# large.net
KiCad netlist of a schematic drawn in EAGLE
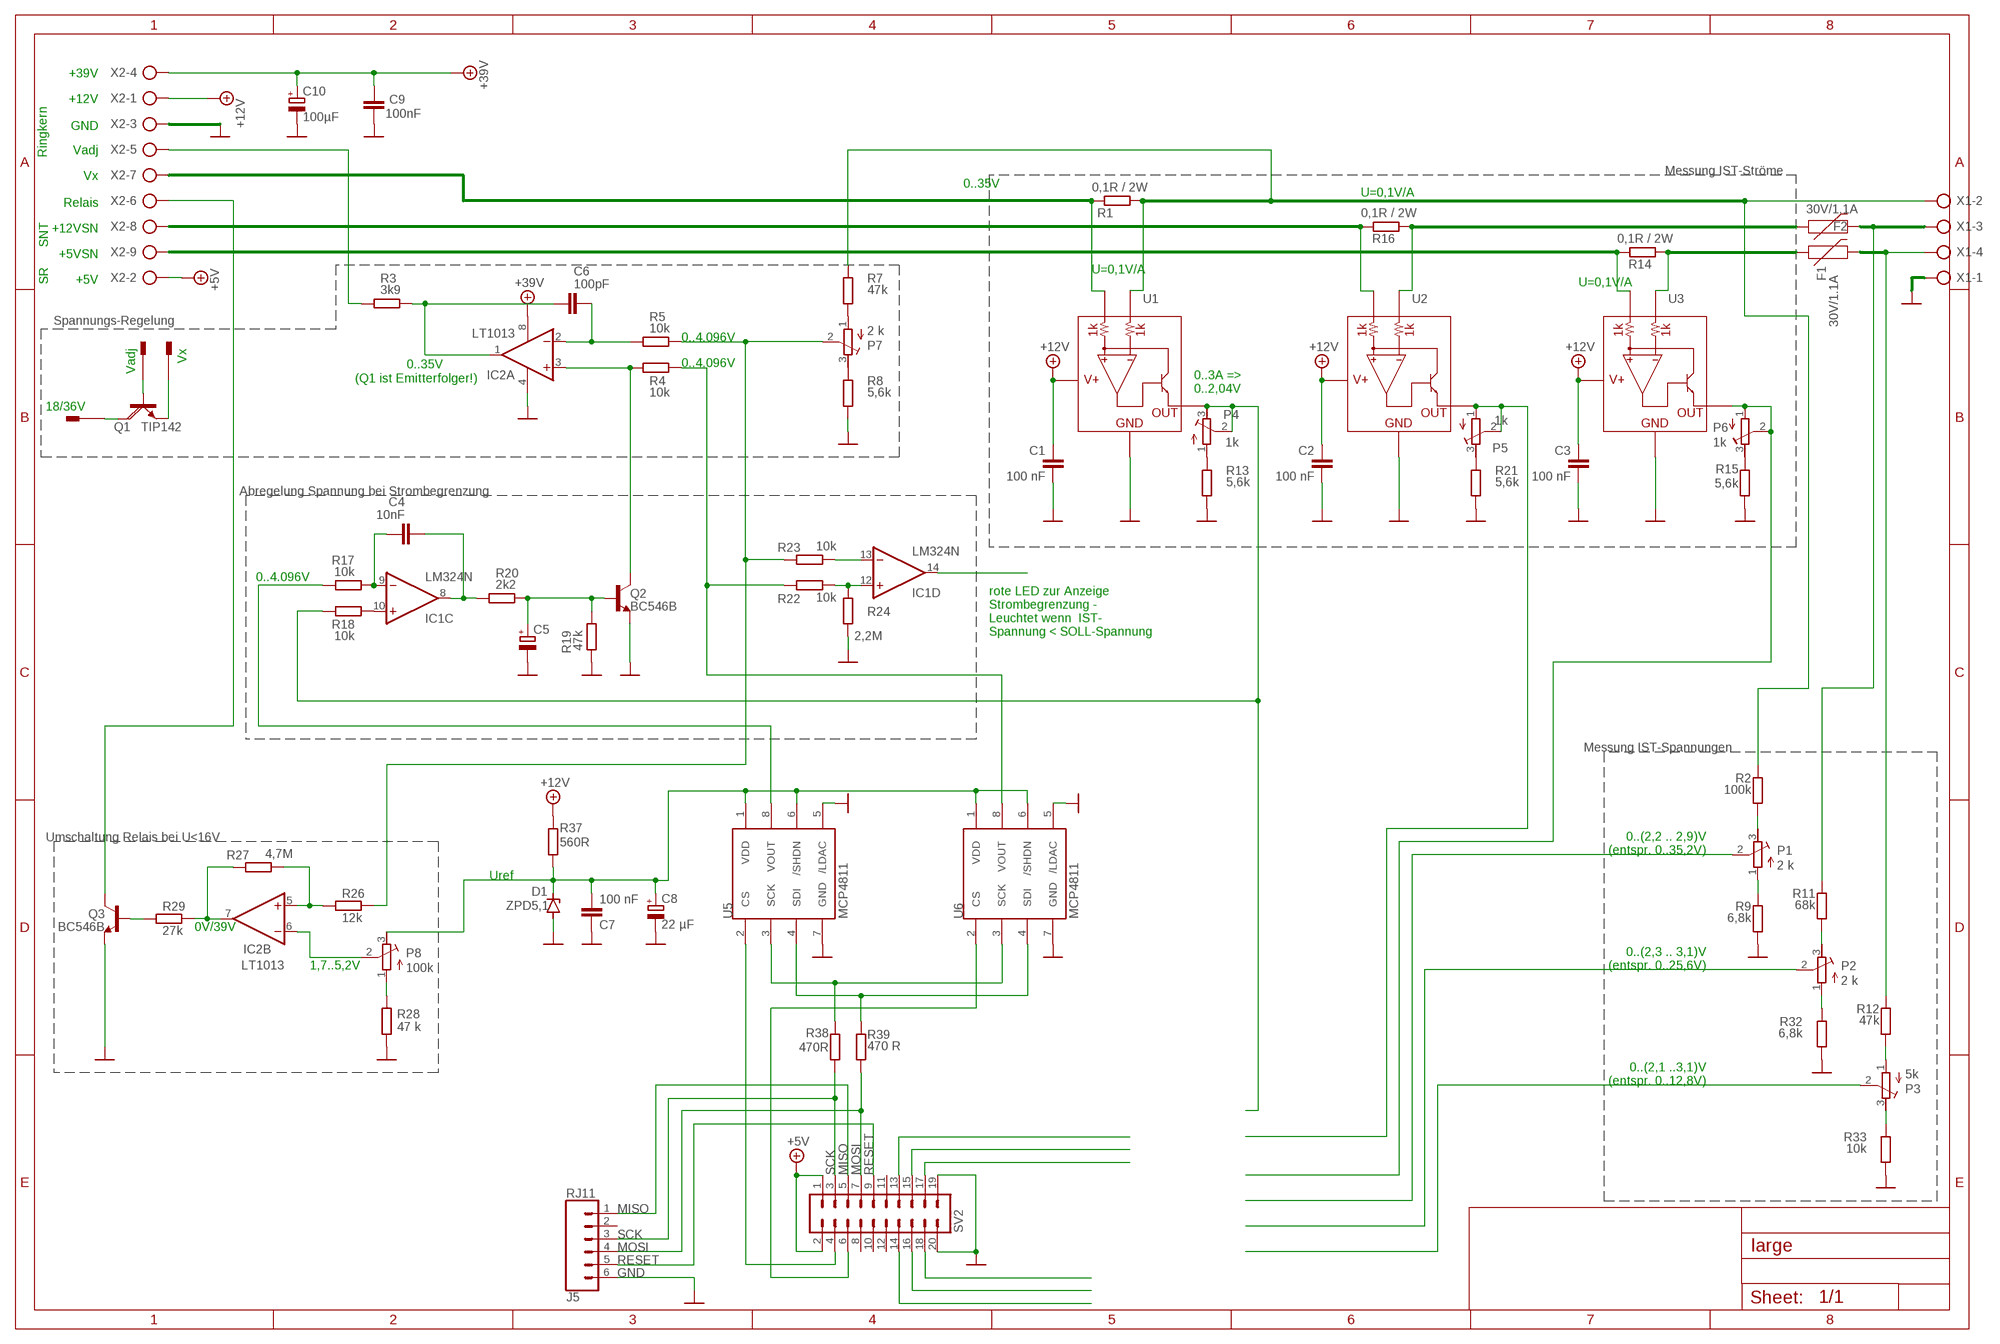
[diagram p0: schematic, sheet 1]

(export (version "E")
  (design (tool "Eeschema 10.0.6"))
  (components
    (comp (ref "C1")
      (value "100 nF")
      (footprint "eagle-import:C025-025X050")
      (libsource (lib "eagle-import") (part "C-EU025-025X050"))
    )
    (comp (ref "C2")
      (value "100 nF")
      (footprint "eagle-import:C025-025X050")
      (libsource (lib "eagle-import") (part "C-EU025-025X050"))
    )
    (comp (ref "C3")
      (value "100 nF")
      (footprint "eagle-import:C025-025X050")
      (libsource (lib "eagle-import") (part "C-EU025-025X050"))
    )
    (comp (ref "C4")
      (value "10nF")
      (footprint "eagle-import:C025-025X050")
      (libsource (lib "eagle-import") (part "C-EU025-025X050"))
    )
    (comp (ref "C5")
      (value "CPOL-EUE2-4")
      (footprint "eagle-import:E2-4")
      (libsource (lib "eagle-import") (part "CPOL-EUE2-4"))
    )
    (comp (ref "C6")
      (value "100pF")
      (footprint "eagle-import:C025-025X050")
      (libsource (lib "eagle-import") (part "C-EU025-025X050"))
    )
    (comp (ref "C7")
      (value "100 nF")
      (footprint "eagle-import:C025-025X050")
      (libsource (lib "eagle-import") (part "C-EU025-025X050"))
    )
    (comp (ref "C8")
      (value "22 µF")
      (footprint "eagle-import:E2-5")
      (libsource (lib "eagle-import") (part "CPOL-EUE2-5"))
    )
    (comp (ref "C9")
      (value "100nF")
      (footprint "eagle-import:C025-025X050")
      (libsource (lib "eagle-import") (part "C-EU025-025X050"))
    )
    (comp (ref "C10")
      (value "100µF")
      (footprint "eagle-import:E2-5")
      (libsource (lib "eagle-import") (part "CPOL-EUE2-5"))
    )
    (comp (ref "D1")
      (value "ZPD5,1")
      (footprint "eagle-import:ZDIO-5")
      (libsource (lib "eagle-import") (part "ZENER-DIODEZD-5"))
    )
    (comp (ref "F1")
      (value "30V/1.1A")
      (footprint "eagle-import:PTH")
      (libsource (lib "eagle-import") (part "PPTC_PTH"))
    )
    (comp (ref "F2")
      (value "30V/1.1A")
      (footprint "eagle-import:PTH")
      (libsource (lib "eagle-import") (part "PPTC_PTH"))
    )
    (comp (ref "IC1")
      (value "LM324N")
      (footprint "eagle-import:DIL14")
      (libsource (lib "eagle-import") (part "LM324N"))
    )
    (comp (ref "IC2")
      (value "LT1013")
      (footprint "eagle-import:DIL08")
      (libsource (lib "eagle-import") (part "OPA1013P"))
    )
    (comp (ref "J2")
      (value "PIN1-2")
      (footprint "eagle-import:62221")
      (fields (field (name "MF") "TYCO ELECTRONICS") (field (name "MPN") "62221-1"))
      (libsource (lib "eagle-import") (part "PIN1-2"))
    )
    (comp (ref "J3")
      (value "PIN1-2")
      (footprint "eagle-import:62221")
      (fields (field (name "MF") "TYCO ELECTRONICS") (field (name "MPN") "62221-1"))
      (libsource (lib "eagle-import") (part "PIN1-2"))
    )
    (comp (ref "J4")
      (value "PIN1-2")
      (footprint "eagle-import:62221")
      (fields (field (name "MF") "TYCO ELECTRONICS") (field (name "MPN") "62221-1"))
      (libsource (lib "eagle-import") (part "PIN1-2"))
    )
    (comp (ref "J5")
      (value "RJ11")
      (footprint "eagle-import:RJ11-6")
      (libsource (lib "eagle-import") (part "RJ11-6"))
    )
    (comp (ref "P1")
      (value "2 k")
      (footprint "eagle-import:RTRIM64Y")
      (libsource (lib "eagle-import") (part "R-TRIMM64Y"))
    )
    (comp (ref "P2")
      (value "2 k")
      (footprint "eagle-import:RTRIM64Y")
      (libsource (lib "eagle-import") (part "R-TRIMM64Y"))
    )
    (comp (ref "P3")
      (value "5k")
      (footprint "eagle-import:RTRIM64Y")
      (libsource (lib "eagle-import") (part "R-TRIMM64Y"))
    )
    (comp (ref "P4")
      (value "1k")
      (footprint "eagle-import:RTRIM64Z")
      (libsource (lib "eagle-import") (part "R-TRIMM64Z"))
    )
    (comp (ref "P5")
      (value "1k")
      (footprint "eagle-import:RTRIM64Y")
      (libsource (lib "eagle-import") (part "R-TRIMM64Y"))
    )
    (comp (ref "P6")
      (value "1k")
      (footprint "eagle-import:RTRIM64Y")
      (libsource (lib "eagle-import") (part "R-TRIMM64Y"))
    )
    (comp (ref "P7")
      (value "2 k")
      (footprint "eagle-import:RTRIM64Y")
      (libsource (lib "eagle-import") (part "R-TRIMM64Y"))
    )
    (comp (ref "P8")
      (value "100k")
      (footprint "eagle-import:RTRIM64Z")
      (libsource (lib "eagle-import") (part "R-TRIMM64Z"))
    )
    (comp (ref "Q1")
      (value "TIP142")
      (footprint "eagle-import:SOT93")
      (libsource (lib "eagle-import") (part "TIP142"))
    )
    (comp (ref "Q2")
      (value "BC546B")
      (footprint "eagle-import:TO92-EBC")
      (libsource (lib "eagle-import") (part "BC546A"))
    )
    (comp (ref "Q3")
      (value "BC546B")
      (footprint "eagle-import:TO92-EBC")
      (libsource (lib "eagle-import") (part "BC546A"))
    )
    (comp (ref "R1")
      (value "0,1R / 2W")
      (footprint "eagle-import:0617_17")
      (libsource (lib "eagle-import") (part "R-EU_0617/17"))
    )
    (comp (ref "R2")
      (value "100k")
      (footprint "eagle-import:0204_7")
      (libsource (lib "eagle-import") (part "R-EU_0204/7"))
    )
    (comp (ref "R3")
      (value "3k9")
      (footprint "eagle-import:0204_7")
      (libsource (lib "eagle-import") (part "R-EU_0204/7"))
    )
    (comp (ref "R4")
      (value "10k")
      (footprint "eagle-import:0204_7")
      (libsource (lib "eagle-import") (part "R-EU_0204/7"))
    )
    (comp (ref "R5")
      (value "10k")
      (footprint "eagle-import:0204_7")
      (libsource (lib "eagle-import") (part "R-EU_0204/7"))
    )
    (comp (ref "R7")
      (value "47k")
      (footprint "eagle-import:0204_7")
      (libsource (lib "eagle-import") (part "R-EU_0204/7"))
    )
    (comp (ref "R8")
      (value "5,6k")
      (footprint "eagle-import:0204_7")
      (libsource (lib "eagle-import") (part "R-EU_0204/7"))
    )
    (comp (ref "R9")
      (value "6,8k")
      (footprint "eagle-import:0204_7")
      (libsource (lib "eagle-import") (part "R-EU_0204/7"))
    )
    (comp (ref "R11")
      (value "68k")
      (footprint "eagle-import:0204_7")
      (libsource (lib "eagle-import") (part "R-EU_0204/7"))
    )
    (comp (ref "R12")
      (value "47k")
      (footprint "eagle-import:0204_7")
      (libsource (lib "eagle-import") (part "R-EU_0204/7"))
    )
    (comp (ref "R13")
      (value "5,6k")
      (footprint "eagle-import:0204_7")
      (libsource (lib "eagle-import") (part "R-EU_0204/7"))
    )
    (comp (ref "R14")
      (value "0,1R / 2W")
      (footprint "eagle-import:0617_17")
      (libsource (lib "eagle-import") (part "R-EU_0617/17"))
    )
    (comp (ref "R15")
      (value "5,6k")
      (footprint "eagle-import:0204_5")
      (libsource (lib "eagle-import") (part "R-EU_0204/5"))
    )
    (comp (ref "R16")
      (value "0,1R / 2W")
      (footprint "eagle-import:0617_17")
      (libsource (lib "eagle-import") (part "R-EU_0617/17"))
    )
    (comp (ref "R17")
      (value "10k")
      (footprint "eagle-import:0204_5")
      (libsource (lib "eagle-import") (part "R-EU_0204/5"))
    )
    (comp (ref "R18")
      (value "10k")
      (footprint "eagle-import:0204_5")
      (libsource (lib "eagle-import") (part "R-EU_0204/5"))
    )
    (comp (ref "R19")
      (value "47k")
      (footprint "eagle-import:0204_5")
      (libsource (lib "eagle-import") (part "R-EU_0204/5"))
    )
    (comp (ref "R20")
      (value "2k2")
      (footprint "eagle-import:0204_5")
      (libsource (lib "eagle-import") (part "R-EU_0204/5"))
    )
    (comp (ref "R21")
      (value "5,6k")
      (footprint "eagle-import:0204_7")
      (libsource (lib "eagle-import") (part "R-EU_0204/7"))
    )
    (comp (ref "R22")
      (value "10k")
      (footprint "eagle-import:0204_5")
      (libsource (lib "eagle-import") (part "R-EU_0204/5"))
    )
    (comp (ref "R23")
      (value "10k")
      (footprint "eagle-import:0204_5")
      (libsource (lib "eagle-import") (part "R-EU_0204/5"))
    )
    (comp (ref "R24")
      (value "2,2M")
      (footprint "eagle-import:0204_5")
      (libsource (lib "eagle-import") (part "R-EU_0204/5"))
    )
    (comp (ref "R26")
      (value "12k")
      (footprint "eagle-import:0204_5")
      (libsource (lib "eagle-import") (part "R-EU_0204/5"))
    )
    (comp (ref "R27")
      (value "4,7M")
      (footprint "eagle-import:0204_5")
      (libsource (lib "eagle-import") (part "R-EU_0204/5"))
    )
    (comp (ref "R28")
      (value "47 k")
      (footprint "eagle-import:0204_5")
      (libsource (lib "eagle-import") (part "R-EU_0204/5"))
    )
    (comp (ref "R29")
      (value "27k")
      (footprint "eagle-import:0204_7")
      (libsource (lib "eagle-import") (part "R-EU_0204/7"))
    )
    (comp (ref "R32")
      (value "6,8k")
      (footprint "eagle-import:0204_7")
      (libsource (lib "eagle-import") (part "R-EU_0204/7"))
    )
    (comp (ref "R33")
      (value "10k")
      (footprint "eagle-import:0204_7")
      (libsource (lib "eagle-import") (part "R-EU_0204/7"))
    )
    (comp (ref "R37")
      (value "560R")
      (footprint "eagle-import:0204_7")
      (libsource (lib "eagle-import") (part "R-EU_0204/7"))
    )
    (comp (ref "R38")
      (value "470R")
      (footprint "eagle-import:0204_7")
      (libsource (lib "eagle-import") (part "R-EU_0204/7"))
    )
    (comp (ref "R39")
      (value "470 R")
      (footprint "eagle-import:0204_7")
      (libsource (lib "eagle-import") (part "R-EU_0204/7"))
    )
    (comp (ref "SV2")
      (value "MA10-2")
      (footprint "eagle-import:MA10-2")
      (libsource (lib "eagle-import") (part "MA10-2"))
    )
    (comp (ref "U1")
      (value "INA139DIL06")
      (footprint "eagle-import:DIL06")
      (libsource (lib "eagle-import") (part "INA139DIL06"))
    )
    (comp (ref "U2")
      (value "INA139DIL06")
      (footprint "eagle-import:DIL06")
      (libsource (lib "eagle-import") (part "INA139DIL06"))
    )
    (comp (ref "U3")
      (value "INA139DIL06")
      (footprint "eagle-import:DIL06")
      (libsource (lib "eagle-import") (part "INA139DIL06"))
    )
    (comp (ref "U5")
      (value "MCP4811")
      (footprint "eagle-import:PDIP8")
      (libsource (lib "eagle-import") (part "MCP4811"))
    )
    (comp (ref "U6")
      (value "MCP4811")
      (footprint "eagle-import:PDIP8")
      (libsource (lib "eagle-import") (part "MCP4811"))
    )
    (comp (ref "X1")
      (value "AK500/4")
      (footprint "eagle-import:AK500_4")
      (libsource (lib "eagle-import") (part "AK500/4"))
    )
    (comp (ref "X2")
      (value "AK500/9")
      (footprint "eagle-import:AK500_9")
      (libsource (lib "eagle-import") (part "AK500/9"))
    )
  )
  (nets
    (net (code "1") (name "+5V") (class "Default")
      (node (ref "SV2") (pin "1") (pinfunction "1_1") (pintype "passive"))
      (node (ref "SV2") (pin "2") (pinfunction "2_2") (pintype "passive"))
      (node (ref "X2") (pin "2") (pinfunction "KL_2") (pintype "passive"))
    )
    (net (code "2") (name "+12V") (class "Default")
      (node (ref "C1") (pin "2") (pinfunction "2_2") (pintype "passive"))
      (node (ref "C2") (pin "2") (pinfunction "2_2") (pintype "passive"))
      (node (ref "C3") (pin "2") (pinfunction "2_2") (pintype "passive"))
      (node (ref "R37") (pin "1") (pinfunction "1_1") (pintype "passive"))
      (node (ref "U1") (pin "6") (pinfunction "V+_6") (pintype "bidirectional"))
      (node (ref "U2") (pin "6") (pinfunction "V+_6") (pintype "bidirectional"))
      (node (ref "U3") (pin "6") (pinfunction "V+_6") (pintype "bidirectional"))
      (node (ref "X2") (pin "1") (pinfunction "KL_1") (pintype "passive"))
    )
    (net (code "3") (name "+39V") (class "Default")
      (node (ref "C10") (pin "+") (pinfunction "+_+") (pintype "passive"))
      (node (ref "C9") (pin "2") (pinfunction "2_2") (pintype "passive"))
      (node (ref "IC2") (pin "8") (pinfunction "V+_8") (pintype "power_in"))
      (node (ref "X2") (pin "4") (pinfunction "KL_4") (pintype "passive"))
    )
    (net (code "4") (name "/MISO") (class "Default")
      (node (ref "J5") (pin "1") (pinfunction "1_1") (pintype "passive"))
      (node (ref "SV2") (pin "5") (pinfunction "5_5") (pintype "passive"))
    )
    (net (code "5") (name "/MOSI") (class "Default")
      (node (ref "J5") (pin "4") (pinfunction "4_4") (pintype "passive"))
      (node (ref "R39") (pin "1") (pinfunction "1_1") (pintype "passive"))
      (node (ref "SV2") (pin "7") (pinfunction "7_7") (pintype "passive"))
    )
    (net (code "6") (name "/RESET") (class "Default")
      (node (ref "J5") (pin "5") (pinfunction "5_5") (pintype "passive"))
      (node (ref "SV2") (pin "9") (pinfunction "9_9") (pintype "passive"))
    )
    (net (code "7") (name "/SCK") (class "Default")
      (node (ref "J5") (pin "3") (pinfunction "3_3") (pintype "passive"))
      (node (ref "R38") (pin "1") (pinfunction "1_1") (pintype "passive"))
      (node (ref "SV2") (pin "3") (pinfunction "3_3") (pintype "passive"))
    )
    (net (code "8") (name "GND") (class "Default")
      (node (ref "C1") (pin "1") (pinfunction "1_1") (pintype "passive"))
      (node (ref "C10") (pin "-") (pinfunction "-_-") (pintype "passive"))
      (node (ref "C2") (pin "1") (pinfunction "1_1") (pintype "passive"))
      (node (ref "C3") (pin "1") (pinfunction "1_1") (pintype "passive"))
      (node (ref "C5") (pin "-") (pinfunction "-_-") (pintype "passive"))
      (node (ref "C7") (pin "2") (pinfunction "2_2") (pintype "passive"))
      (node (ref "C8") (pin "-") (pinfunction "-_-") (pintype "passive"))
      (node (ref "C9") (pin "1") (pinfunction "1_1") (pintype "passive"))
      (node (ref "D1") (pin "A") (pinfunction "A_A") (pintype "passive"))
      (node (ref "IC2") (pin "4") (pinfunction "V-_4") (pintype "power_in"))
      (node (ref "J5") (pin "6") (pinfunction "6_6") (pintype "passive"))
      (node (ref "Q2") (pin "E") (pinfunction "E_E") (pintype "passive"))
      (node (ref "Q3") (pin "E") (pinfunction "E_E") (pintype "passive"))
      (node (ref "R13") (pin "1") (pinfunction "1_1") (pintype "passive"))
      (node (ref "R15") (pin "1") (pinfunction "1_1") (pintype "passive"))
      (node (ref "R19") (pin "2") (pinfunction "2_2") (pintype "passive"))
      (node (ref "R21") (pin "1") (pinfunction "1_1") (pintype "passive"))
      (node (ref "R24") (pin "1") (pinfunction "1_1") (pintype "passive"))
      (node (ref "R28") (pin "1") (pinfunction "1_1") (pintype "passive"))
      (node (ref "R32") (pin "1") (pinfunction "1_1") (pintype "passive"))
      (node (ref "R33") (pin "1") (pinfunction "1_1") (pintype "passive"))
      (node (ref "R8") (pin "1") (pinfunction "1_1") (pintype "passive"))
      (node (ref "R9") (pin "1") (pinfunction "1_1") (pintype "passive"))
      (node (ref "SV2") (pin "19") (pinfunction "19_19") (pintype "passive"))
      (node (ref "SV2") (pin "20") (pinfunction "20_20") (pintype "passive"))
      (node (ref "U1") (pin "2") (pinfunction "GND_2") (pintype "bidirectional"))
      (node (ref "U2") (pin "2") (pinfunction "GND_2") (pintype "bidirectional"))
      (node (ref "U3") (pin "2") (pinfunction "GND_2") (pintype "bidirectional"))
      (node (ref "U5") (pin "5") (pinfunction "/LDAC_5") (pintype "bidirectional"))
      (node (ref "U5") (pin "7") (pinfunction "GND_7") (pintype "bidirectional"))
      (node (ref "U6") (pin "5") (pinfunction "/LDAC_5") (pintype "bidirectional"))
      (node (ref "U6") (pin "7") (pinfunction "GND_7") (pintype "bidirectional"))
      (node (ref "X1") (pin "1") (pinfunction "KL_1") (pintype "passive"))
      (node (ref "X2") (pin "3") (pinfunction "KL_3") (pintype "passive"))
    )
    (net (code "9") (name "Net-(C5-Pad+)") (class "Default")
      (node (ref "C5") (pin "+") (pinfunction "+_+") (pintype "passive"))
      (node (ref "Q2") (pin "B") (pinfunction "B_B") (pintype "passive"))
      (node (ref "R19") (pin "1") (pinfunction "1_1") (pintype "passive"))
      (node (ref "R20") (pin "2") (pinfunction "2_2") (pintype "passive"))
    )
    (net (code "10") (name "Net-(F1-1)") (class "Default")
      (node (ref "F1") (pin "P$1") (pinfunction "1_P$1") (pintype "bidirectional"))
      (node (ref "R14") (pin "1") (pinfunction "1_1") (pintype "passive"))
      (node (ref "U3") (pin "4") (pinfunction "VIN-_4") (pintype "bidirectional"))
    )
    (net (code "11") (name "Net-(F1-2)") (class "Default")
      (node (ref "F1") (pin "P$2") (pinfunction "2_P$2") (pintype "bidirectional"))
      (node (ref "R12") (pin "2") (pinfunction "2_2") (pintype "passive"))
      (node (ref "X1") (pin "4") (pinfunction "KL_4") (pintype "passive"))
    )
    (net (code "12") (name "Net-(F2-1)") (class "Default")
      (node (ref "F2") (pin "P$1") (pinfunction "1_P$1") (pintype "bidirectional"))
      (node (ref "R16") (pin "1") (pinfunction "1_1") (pintype "passive"))
      (node (ref "U2") (pin "4") (pinfunction "VIN-_4") (pintype "bidirectional"))
    )
    (net (code "13") (name "Net-(F2-2)") (class "Default")
      (node (ref "F2") (pin "P$2") (pinfunction "2_P$2") (pintype "bidirectional"))
      (node (ref "R11") (pin "2") (pinfunction "2_2") (pintype "passive"))
      (node (ref "X1") (pin "3") (pinfunction "KL_3") (pintype "passive"))
    )
    (net (code "14") (name "Net-(IC1C-+IN)") (class "Default")
      (node (ref "IC1") (pin "10") (pinfunction "+IN_10") (pintype "input"))
      (node (ref "R18") (pin "1") (pinfunction "1_1") (pintype "passive"))
    )
    (net (code "15") (name "Net-(IC1C--IN)") (class "Default")
      (node (ref "C4") (pin "2") (pinfunction "2_2") (pintype "passive"))
      (node (ref "IC1") (pin "9") (pinfunction "-IN_9") (pintype "input"))
      (node (ref "R17") (pin "1") (pinfunction "1_1") (pintype "passive"))
    )
    (net (code "16") (name "Net-(IC1C-OUT)") (class "Default")
      (node (ref "C4") (pin "1") (pinfunction "1_1") (pintype "passive"))
      (node (ref "IC1") (pin "8") (pinfunction "OUT_8") (pintype "output"))
      (node (ref "R20") (pin "1") (pinfunction "1_1") (pintype "passive"))
    )
    (net (code "17") (name "Net-(IC1D-+IN)") (class "Default")
      (node (ref "IC1") (pin "12") (pinfunction "+IN_12") (pintype "input"))
      (node (ref "R22") (pin "2") (pinfunction "2_2") (pintype "passive"))
      (node (ref "R24") (pin "2") (pinfunction "2_2") (pintype "passive"))
    )
    (net (code "18") (name "Net-(IC1D--IN)") (class "Default")
      (node (ref "IC1") (pin "13") (pinfunction "-IN_13") (pintype "input"))
      (node (ref "R23") (pin "2") (pinfunction "2_2") (pintype "passive"))
    )
    (net (code "19") (name "Net-(IC2A-+IN)") (class "Default")
      (node (ref "IC2") (pin "3") (pinfunction "+IN_3") (pintype "input"))
      (node (ref "Q2") (pin "C") (pinfunction "C_C") (pintype "passive"))
      (node (ref "R4") (pin "1") (pinfunction "1_1") (pintype "passive"))
    )
    (net (code "20") (name "Net-(IC2A--IN)") (class "Default")
      (node (ref "C6") (pin "2") (pinfunction "2_2") (pintype "passive"))
      (node (ref "IC2") (pin "2") (pinfunction "-IN_2") (pintype "input"))
      (node (ref "R5") (pin "1") (pinfunction "1_1") (pintype "passive"))
    )
    (net (code "21") (name "Net-(IC2A-OUT)") (class "Default")
      (node (ref "C6") (pin "1") (pinfunction "1_1") (pintype "passive"))
      (node (ref "IC2") (pin "1") (pinfunction "OUT_1") (pintype "output"))
      (node (ref "R3") (pin "2") (pinfunction "2_2") (pintype "passive"))
    )
    (net (code "22") (name "Net-(IC2B-+IN)") (class "Default")
      (node (ref "IC2") (pin "5") (pinfunction "+IN_5") (pintype "input"))
      (node (ref "R26") (pin "1") (pinfunction "1_1") (pintype "passive"))
      (node (ref "R27") (pin "2") (pinfunction "2_2") (pintype "passive"))
    )
    (net (code "23") (name "Net-(IC2B--IN)") (class "Default")
      (node (ref "IC2") (pin "6") (pinfunction "-IN_6") (pintype "input"))
      (node (ref "P8") (pin "2") (pinfunction "S_2") (pintype "passive"))
    )
    (net (code "24") (name "Net-(IC2B-OUT)") (class "Default")
      (node (ref "IC2") (pin "7") (pinfunction "OUT_7") (pintype "output"))
      (node (ref "R27") (pin "1") (pinfunction "1_1") (pintype "passive"))
      (node (ref "R29") (pin "2") (pinfunction "2_2") (pintype "passive"))
    )
    (net (code "25") (name "Net-(J2-Pad1)") (class "Default")
      (node (ref "J2") (pin "1") (pinfunction "1_1") (pintype "passive"))
      (node (ref "Q1") (pin "C") (pinfunction "C_C") (pintype "passive"))
    )
    (net (code "26") (name "Net-(J3-Pad1)") (class "Default")
      (node (ref "J3") (pin "1") (pinfunction "1_1") (pintype "passive"))
      (node (ref "Q1") (pin "B") (pinfunction "B_B") (pintype "passive"))
    )
    (net (code "27") (name "Net-(J4-Pad1)") (class "Default")
      (node (ref "J4") (pin "1") (pinfunction "1_1") (pintype "passive"))
      (node (ref "Q1") (pin "E") (pinfunction "E_E") (pintype "passive"))
    )
    (net (code "28") (name "Net-(P1-A)") (class "Default")
      (node (ref "P1") (pin "1") (pinfunction "A_1") (pintype "passive"))
      (node (ref "R9") (pin "2") (pinfunction "2_2") (pintype "passive"))
    )
    (net (code "29") (name "Net-(P1-E)") (class "Default")
      (node (ref "P1") (pin "3") (pinfunction "E_3") (pintype "passive"))
      (node (ref "R2") (pin "1") (pinfunction "1_1") (pintype "passive"))
    )
    (net (code "30") (name "Net-(P2-A)") (class "Default")
      (node (ref "P2") (pin "1") (pinfunction "A_1") (pintype "passive"))
      (node (ref "R32") (pin "2") (pinfunction "2_2") (pintype "passive"))
    )
    (net (code "31") (name "Net-(P2-E)") (class "Default")
      (node (ref "P2") (pin "3") (pinfunction "E_3") (pintype "passive"))
      (node (ref "R11") (pin "1") (pinfunction "1_1") (pintype "passive"))
    )
    (net (code "32") (name "Net-(P3-A)") (class "Default")
      (node (ref "P3") (pin "1") (pinfunction "A_1") (pintype "passive"))
      (node (ref "R12") (pin "1") (pinfunction "1_1") (pintype "passive"))
    )
    (net (code "33") (name "Net-(P3-E)") (class "Default")
      (node (ref "P3") (pin "3") (pinfunction "E_3") (pintype "passive"))
      (node (ref "R33") (pin "2") (pinfunction "2_2") (pintype "passive"))
    )
    (net (code "34") (name "Net-(P4-A)") (class "Default")
      (node (ref "P4") (pin "1") (pinfunction "A_1") (pintype "passive"))
      (node (ref "R13") (pin "2") (pinfunction "2_2") (pintype "passive"))
    )
    (net (code "35") (name "Net-(P4-E)") (class "Default")
      (node (ref "P4") (pin "2") (pinfunction "S_2") (pintype "passive"))
      (node (ref "P4") (pin "3") (pinfunction "E_3") (pintype "passive"))
      (node (ref "R18") (pin "2") (pinfunction "2_2") (pintype "passive"))
      (node (ref "U1") (pin "1") (pinfunction "OUT_1") (pintype "bidirectional"))
    )
    (net (code "36") (name "Net-(P5-A)") (class "Default")
      (node (ref "P5") (pin "1") (pinfunction "A_1") (pintype "passive"))
      (node (ref "P5") (pin "2") (pinfunction "S_2") (pintype "passive"))
      (node (ref "U2") (pin "1") (pinfunction "OUT_1") (pintype "bidirectional"))
    )
    (net (code "37") (name "Net-(P5-E)") (class "Default")
      (node (ref "P5") (pin "3") (pinfunction "E_3") (pintype "passive"))
      (node (ref "R21") (pin "2") (pinfunction "2_2") (pintype "passive"))
    )
    (net (code "38") (name "Net-(P6-A)") (class "Default")
      (node (ref "P6") (pin "1") (pinfunction "A_1") (pintype "passive"))
      (node (ref "P6") (pin "2") (pinfunction "S_2") (pintype "passive"))
      (node (ref "U3") (pin "1") (pinfunction "OUT_1") (pintype "bidirectional"))
    )
    (net (code "39") (name "Net-(P6-E)") (class "Default")
      (node (ref "P6") (pin "3") (pinfunction "E_3") (pintype "passive"))
      (node (ref "R15") (pin "2") (pinfunction "2_2") (pintype "passive"))
    )
    (net (code "40") (name "Net-(P7-A)") (class "Default")
      (node (ref "P7") (pin "1") (pinfunction "A_1") (pintype "passive"))
      (node (ref "R7") (pin "1") (pinfunction "1_1") (pintype "passive"))
    )
    (net (code "41") (name "Net-(P7-E)") (class "Default")
      (node (ref "P7") (pin "3") (pinfunction "E_3") (pintype "passive"))
      (node (ref "R8") (pin "2") (pinfunction "2_2") (pintype "passive"))
    )
    (net (code "42") (name "Net-(P7-S)") (class "Default")
      (node (ref "P7") (pin "2") (pinfunction "S_2") (pintype "passive"))
      (node (ref "R23") (pin "1") (pinfunction "1_1") (pintype "passive"))
      (node (ref "R26") (pin "2") (pinfunction "2_2") (pintype "passive"))
      (node (ref "R5") (pin "2") (pinfunction "2_2") (pintype "passive"))
    )
    (net (code "43") (name "Net-(P8-A)") (class "Default")
      (node (ref "P8") (pin "1") (pinfunction "A_1") (pintype "passive"))
      (node (ref "R28") (pin "2") (pinfunction "2_2") (pintype "passive"))
    )
    (net (code "44") (name "Net-(P8-E)") (class "Default")
      (node (ref "C7") (pin "1") (pinfunction "1_1") (pintype "passive"))
      (node (ref "C8") (pin "+") (pinfunction "+_+") (pintype "passive"))
      (node (ref "D1") (pin "C") (pinfunction "C_C") (pintype "passive"))
      (node (ref "P8") (pin "3") (pinfunction "E_3") (pintype "passive"))
      (node (ref "R37") (pin "2") (pinfunction "2_2") (pintype "passive"))
      (node (ref "U5") (pin "1") (pinfunction "VDD_1") (pintype "bidirectional"))
      (node (ref "U5") (pin "6") (pinfunction "/SHDN_6") (pintype "bidirectional"))
      (node (ref "U6") (pin "1") (pinfunction "VDD_1") (pintype "bidirectional"))
      (node (ref "U6") (pin "6") (pinfunction "/SHDN_6") (pintype "bidirectional"))
    )
    (net (code "45") (name "Net-(Q3-PadB)") (class "Default")
      (node (ref "Q3") (pin "B") (pinfunction "B_B") (pintype "passive"))
      (node (ref "R29") (pin "1") (pinfunction "1_1") (pintype "passive"))
    )
    (net (code "46") (name "Net-(U1-VIN+)") (class "Default")
      (node (ref "R1") (pin "2") (pinfunction "2_2") (pintype "passive"))
      (node (ref "U1") (pin "3") (pinfunction "VIN+_3") (pintype "bidirectional"))
      (node (ref "X2") (pin "7") (pinfunction "KL_7") (pintype "passive"))
    )
    (net (code "47") (name "Net-(U1-VIN-)") (class "Default")
      (node (ref "R1") (pin "1") (pinfunction "1_1") (pintype "passive"))
      (node (ref "R2") (pin "2") (pinfunction "2_2") (pintype "passive"))
      (node (ref "R7") (pin "2") (pinfunction "2_2") (pintype "passive"))
      (node (ref "U1") (pin "4") (pinfunction "VIN-_4") (pintype "bidirectional"))
      (node (ref "X1") (pin "2") (pinfunction "KL_2") (pintype "passive"))
    )
    (net (code "48") (name "Net-(U2-VIN+)") (class "Default")
      (node (ref "R16") (pin "2") (pinfunction "2_2") (pintype "passive"))
      (node (ref "U2") (pin "3") (pinfunction "VIN+_3") (pintype "bidirectional"))
      (node (ref "X2") (pin "8") (pinfunction "KL_8") (pintype "passive"))
    )
    (net (code "49") (name "Net-(U3-VIN+)") (class "Default")
      (node (ref "R14") (pin "2") (pinfunction "2_2") (pintype "passive"))
      (node (ref "U3") (pin "3") (pinfunction "VIN+_3") (pintype "bidirectional"))
      (node (ref "X2") (pin "9") (pinfunction "KL_9") (pintype "passive"))
    )
    (net (code "50") (name "Net-(U5-CS)") (class "Default")
      (node (ref "SV2") (pin "4") (pinfunction "4_4") (pintype "passive"))
      (node (ref "U5") (pin "2") (pinfunction "CS_2") (pintype "bidirectional"))
    )
    (net (code "51") (name "Net-(U5-SCK)") (class "Default")
      (node (ref "R38") (pin "2") (pinfunction "2_2") (pintype "passive"))
      (node (ref "U5") (pin "3") (pinfunction "SCK_3") (pintype "bidirectional"))
      (node (ref "U6") (pin "3") (pinfunction "SCK_3") (pintype "bidirectional"))
    )
    (net (code "52") (name "Net-(U5-SDI)") (class "Default")
      (node (ref "R39") (pin "2") (pinfunction "2_2") (pintype "passive"))
      (node (ref "U5") (pin "4") (pinfunction "SDI_4") (pintype "bidirectional"))
      (node (ref "U6") (pin "4") (pinfunction "SDI_4") (pintype "bidirectional"))
    )
    (net (code "53") (name "Net-(U5-VOUT)") (class "Default")
      (node (ref "R17") (pin "2") (pinfunction "2_2") (pintype "passive"))
      (node (ref "U5") (pin "8") (pinfunction "VOUT_8") (pintype "bidirectional"))
    )
    (net (code "54") (name "Net-(U6-CS)") (class "Default")
      (node (ref "SV2") (pin "6") (pinfunction "6_6") (pintype "passive"))
      (node (ref "U6") (pin "2") (pinfunction "CS_2") (pintype "bidirectional"))
    )
    (net (code "55") (name "Net-(U6-VOUT)") (class "Default")
      (node (ref "R22") (pin "1") (pinfunction "1_1") (pintype "passive"))
      (node (ref "R4") (pin "2") (pinfunction "2_2") (pintype "passive"))
      (node (ref "U6") (pin "8") (pinfunction "VOUT_8") (pintype "bidirectional"))
    )
    (net (code "56") (name "Net-(X2E-KL)") (class "Default")
      (node (ref "R3") (pin "1") (pinfunction "1_1") (pintype "passive"))
      (node (ref "X2") (pin "5") (pinfunction "KL_5") (pintype "passive"))
    )
    (net (code "57") (name "Net-(X2F-KL)") (class "Default")
      (node (ref "Q3") (pin "C") (pinfunction "C_C") (pintype "passive"))
      (node (ref "X2") (pin "6") (pinfunction "KL_6") (pintype "passive"))
    )
    (net (code "58") (name "unconnected-(IC1D-OUT-Pad14)") (class "Default")
      (node (ref "IC1") (pin "14") (pinfunction "OUT_14") (pintype "output"))
    )
    (net (code "59") (name "unconnected-(J5-Pad2)") (class "Default")
      (node (ref "J5") (pin "2") (pinfunction "2_2") (pintype "passive"))
    )
    (net (code "60") (name "unconnected-(P1-S-Pad2)") (class "Default")
      (node (ref "P1") (pin "2") (pinfunction "S_2") (pintype "passive"))
    )
    (net (code "61") (name "unconnected-(P2-S-Pad2)") (class "Default")
      (node (ref "P2") (pin "2") (pinfunction "S_2") (pintype "passive"))
    )
    (net (code "62") (name "unconnected-(P3-S-Pad2)") (class "Default")
      (node (ref "P3") (pin "2") (pinfunction "S_2") (pintype "passive"))
    )
    (net (code "63") (name "unconnected-(SV2-Pad8)") (class "Default")
      (node (ref "SV2") (pin "8") (pinfunction "8_8") (pintype "passive"))
    )
    (net (code "64") (name "unconnected-(SV2-Pad10)") (class "Default")
      (node (ref "SV2") (pin "10") (pinfunction "10_10") (pintype "passive"))
    )
    (net (code "65") (name "unconnected-(SV2-Pad11)") (class "Default")
      (node (ref "SV2") (pin "11") (pinfunction "11_11") (pintype "passive"))
    )
    (net (code "66") (name "unconnected-(SV2-Pad12)") (class "Default")
      (node (ref "SV2") (pin "12") (pinfunction "12_12") (pintype "passive"))
    )
    (net (code "67") (name "unconnected-(SV2-Pad13)") (class "Default")
      (node (ref "SV2") (pin "13") (pinfunction "13_13") (pintype "passive"))
    )
    (net (code "68") (name "unconnected-(SV2-Pad14)") (class "Default")
      (node (ref "SV2") (pin "14") (pinfunction "14_14") (pintype "passive"))
    )
    (net (code "69") (name "unconnected-(SV2-Pad15)") (class "Default")
      (node (ref "SV2") (pin "15") (pinfunction "15_15") (pintype "passive"))
    )
    (net (code "70") (name "unconnected-(SV2-Pad16)") (class "Default")
      (node (ref "SV2") (pin "16") (pinfunction "16_16") (pintype "passive"))
    )
    (net (code "71") (name "unconnected-(SV2-Pad17)") (class "Default")
      (node (ref "SV2") (pin "17") (pinfunction "17_17") (pintype "passive"))
    )
    (net (code "72") (name "unconnected-(SV2-Pad18)") (class "Default")
      (node (ref "SV2") (pin "18") (pinfunction "18_18") (pintype "passive"))
    )
  )
)
